# finger_jlink_r1_4.net
KiCad netlist of a schematic drawn in EAGLE
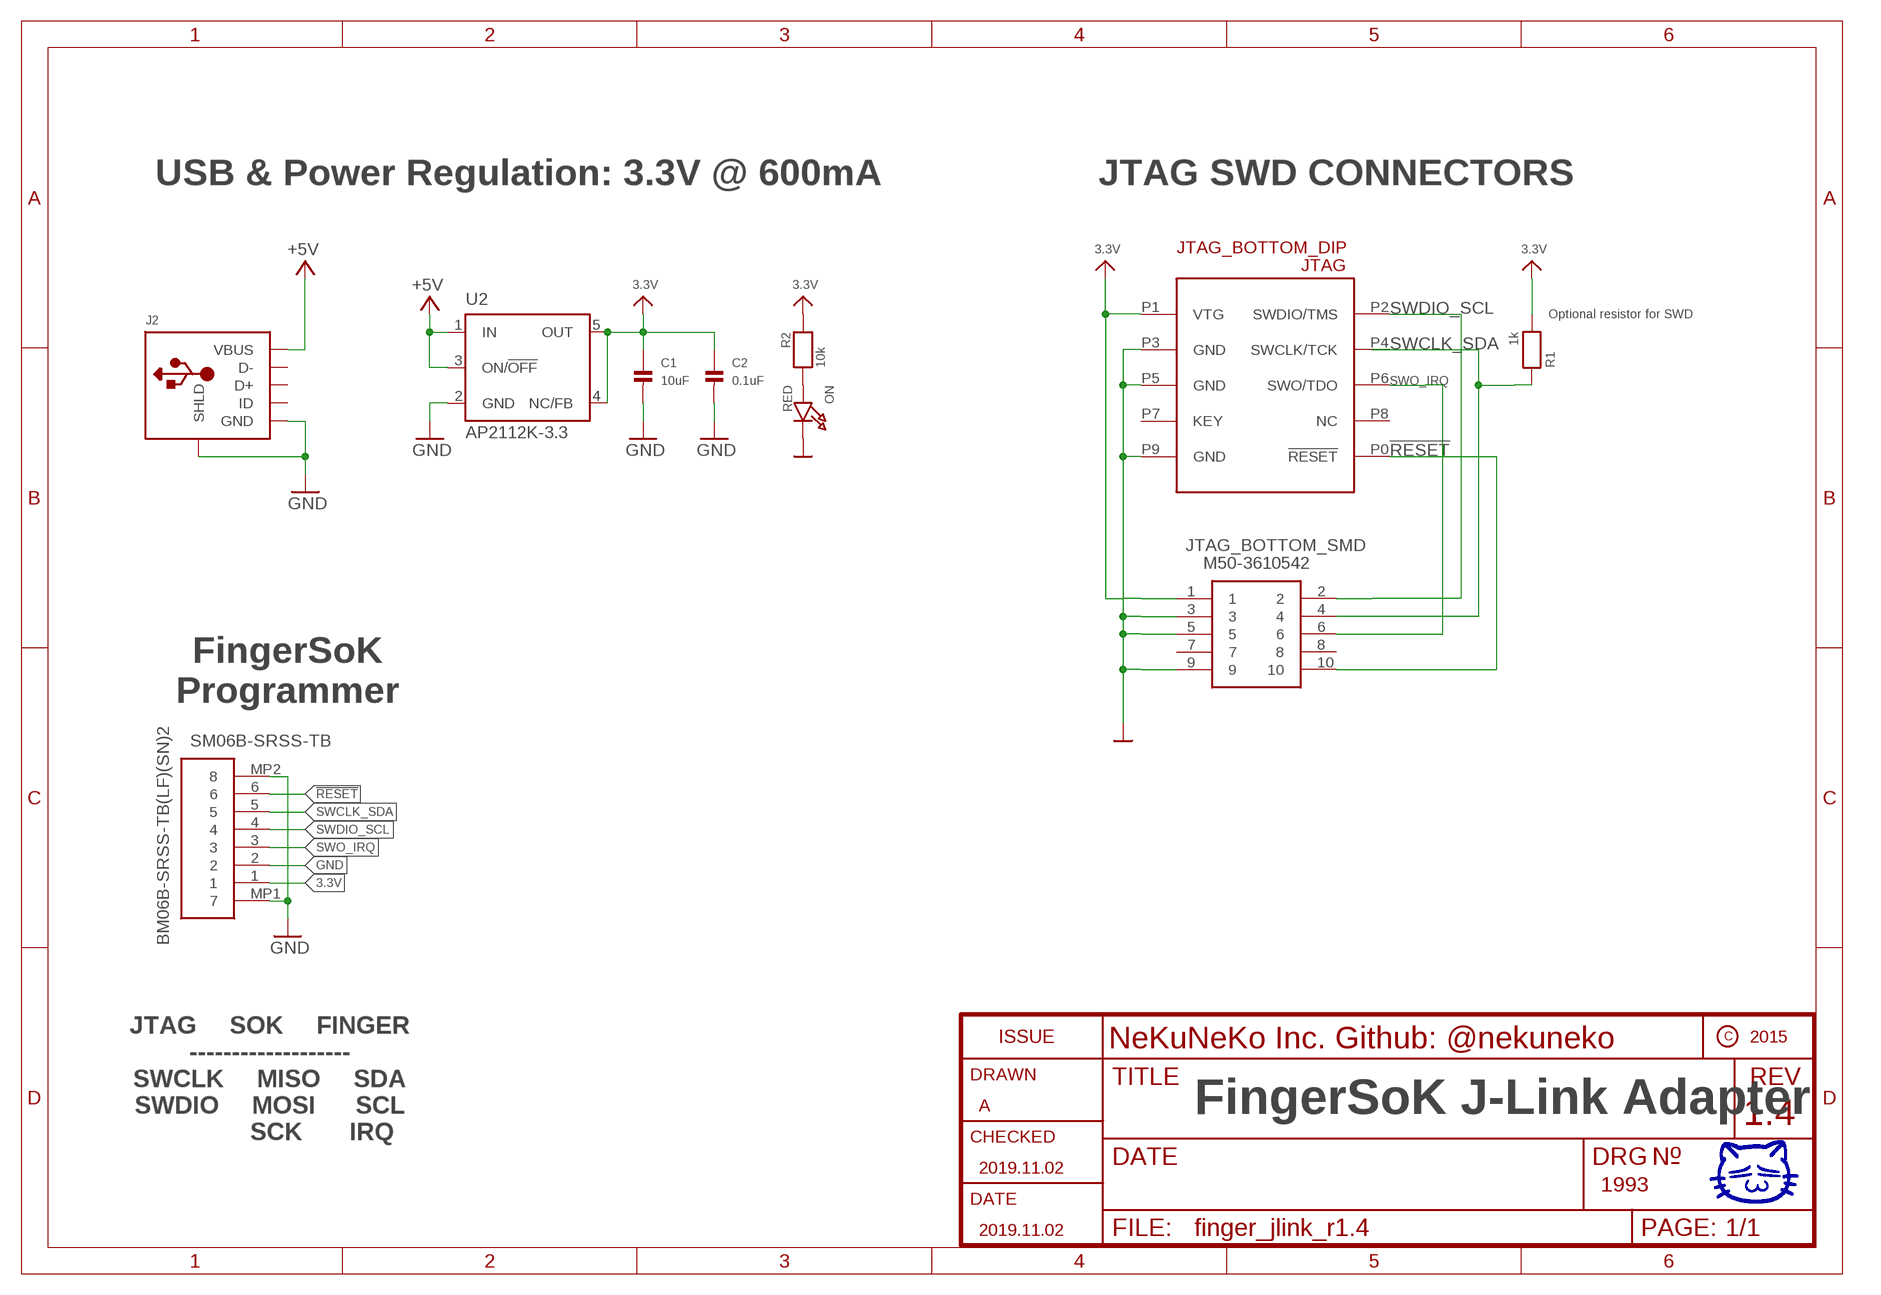
[diagram p0: schematic, sheet 1]

(export (version "E")
  (design (tool "Eeschema 10.0.6"))
  (components
    (comp (ref "C1")
      (value "10uF")
      (footprint "eagle-import:_0402")
      (libsource (lib "eagle-import") (part "CAP_CERAMIC_0402"))
    )
    (comp (ref "C2")
      (value "0.1uF")
      (footprint "eagle-import:_0402")
      (libsource (lib "eagle-import") (part "CAP_CERAMIC_0402"))
    )
    (comp (ref "J2")
      (value "FLAT_MICROUSB_ALIEXPRESS_TYPE_4")
      (footprint "eagle-import:USB_TYPE_4_105164-0001")
      (libsource (lib "eagle-import") (part "FLAT_MICROUSB_ALIEXPRESS_TYPE_4"))
    )
    (comp (ref "JTAG_BOTTOM_DIP")
      (value "JTAGICE3-CONNECTOR50MIL-THT")
      (footprint "eagle-import:JTAGICE3-50MIL")
      (libsource (lib "eagle-import") (part "JTAGICE3-CONNECTOR50MIL-THT"))
    )
    (comp (ref "JTAG_BOTTOM_SMD")
      (value "M50-3610542")
      (footprint "eagle-import:M503610542")
      (fields (field (name "MOUSER_PART_NUMBER") "855-M50-3610542"))
      (libsource (lib "eagle-import") (part "M50-3610542"))
    )
    (comp (ref "ON")
      (value "RED")
      (footprint "eagle-import:CHIPLED_0603")
      (libsource (lib "eagle-import") (part "LED0603"))
    )
    (comp (ref "R1")
      (value "1k")
      (footprint "eagle-import:_0402")
      (libsource (lib "eagle-import") (part "RESISTOR_0402"))
    )
    (comp (ref "R2")
      (value "10k")
      (footprint "eagle-import:_0402")
      (libsource (lib "eagle-import") (part "RESISTOR_0402"))
    )
    (comp (ref "SM06B-SRSS-TB")
      (value "BM06B-SRSS-TB(LF)(SN)2")
      (footprint "eagle-import:BM06B-SRSS-TB(LF)(SN)_2")
      (libsource (lib "eagle-import") (part "BM06B-SRSS-TB(LF)(SN)2"))
    )
    (comp (ref "U2")
      (value "AP2112K-3.3")
      (footprint "eagle-import:SOT23-DBV")
      (libsource (lib "eagle-import") (part "LP2985-XXDBVR33"))
    )
  )
  (nets
    (net (code "1") (name "+5V") (class "Default")
      (node (ref "J2") (pin "P$5") (pinfunction "VBUS_P$5") (pintype "power_in"))
      (node (ref "U2") (pin "1") (pinfunction "IN_1") (pintype "input"))
      (node (ref "U2") (pin "3") (pinfunction "ON/~{OFF}_3") (pintype "input"))
    )
    (net (code "2") (name "/~{RESET}") (class "Default")
      (node (ref "JTAG_BOTTOM_DIP") (pin "P0") (pinfunction "~{RESET}_P0") (pintype "bidirectional"))
      (node (ref "JTAG_BOTTOM_SMD") (pin "10") (pinfunction "10_10") (pintype "bidirectional"))
      (node (ref "SM06B-SRSS-TB") (pin "6") (pinfunction "6_6") (pintype "bidirectional"))
    )
    (net (code "3") (name "3.3V") (class "Default")
      (node (ref "C1") (pin "1") (pinfunction "P$1_1") (pintype "passive"))
      (node (ref "C2") (pin "1") (pinfunction "P$1_1") (pintype "passive"))
      (node (ref "JTAG_BOTTOM_DIP") (pin "P1") (pinfunction "VTG_P1") (pintype "bidirectional"))
      (node (ref "JTAG_BOTTOM_SMD") (pin "1") (pinfunction "1_1") (pintype "bidirectional"))
      (node (ref "R1") (pin "2") (pinfunction "2_2") (pintype "passive"))
      (node (ref "R2") (pin "2") (pinfunction "2_2") (pintype "passive"))
      (node (ref "SM06B-SRSS-TB") (pin "1") (pinfunction "1_1") (pintype "bidirectional"))
      (node (ref "U2") (pin "4") (pinfunction "NC/FB_4") (pintype "passive"))
      (node (ref "U2") (pin "5") (pinfunction "OUT_5") (pintype "passive"))
    )
    (net (code "4") (name "GND") (class "Default")
      (node (ref "C1") (pin "2") (pinfunction "P$2_2") (pintype "passive"))
      (node (ref "C2") (pin "2") (pinfunction "P$2_2") (pintype "passive"))
      (node (ref "J2") (pin "P$1") (pinfunction "GND_P$1") (pintype "power_in"))
      (node (ref "J2") (pin "P$8") (pinfunction "SHLD_P$8") (pintype "power_in"))
      (node (ref "J2") (pin "P$9") (pinfunction "SHLD_P$9") (pintype "power_in"))
      (node (ref "JTAG_BOTTOM_DIP") (pin "P3") (pinfunction "GND_P3") (pintype "bidirectional"))
      (node (ref "JTAG_BOTTOM_DIP") (pin "P5") (pinfunction "GND_P5") (pintype "bidirectional"))
      (node (ref "JTAG_BOTTOM_DIP") (pin "P9") (pinfunction "GND_P9") (pintype "bidirectional"))
      (node (ref "JTAG_BOTTOM_SMD") (pin "3") (pinfunction "3_3") (pintype "bidirectional"))
      (node (ref "JTAG_BOTTOM_SMD") (pin "5") (pinfunction "5_5") (pintype "bidirectional"))
      (node (ref "JTAG_BOTTOM_SMD") (pin "9") (pinfunction "9_9") (pintype "bidirectional"))
      (node (ref "ON") (pin "C") (pinfunction "C_C") (pintype "passive"))
      (node (ref "SM06B-SRSS-TB") (pin "2") (pinfunction "2_2") (pintype "bidirectional"))
      (node (ref "SM06B-SRSS-TB") (pin "MP1") (pinfunction "7_MP1") (pintype "bidirectional"))
      (node (ref "SM06B-SRSS-TB") (pin "MP2") (pinfunction "8_MP2") (pintype "bidirectional"))
      (node (ref "U2") (pin "2") (pinfunction "GND_2") (pintype "power_in"))
    )
    (net (code "5") (name "Net-(ON-PadA)") (class "Default")
      (node (ref "ON") (pin "A") (pinfunction "A_A") (pintype "passive"))
      (node (ref "R2") (pin "1") (pinfunction "1_1") (pintype "passive"))
    )
    (net (code "6") (name "SWCLK_SDA") (class "Default")
      (node (ref "JTAG_BOTTOM_DIP") (pin "P4") (pinfunction "SWCLK/TCK_P4") (pintype "bidirectional"))
      (node (ref "JTAG_BOTTOM_SMD") (pin "4") (pinfunction "4_4") (pintype "bidirectional"))
      (node (ref "R1") (pin "1") (pinfunction "1_1") (pintype "passive"))
      (node (ref "SM06B-SRSS-TB") (pin "5") (pinfunction "5_5") (pintype "bidirectional"))
    )
    (net (code "7") (name "SWDIO_SCL") (class "Default")
      (node (ref "JTAG_BOTTOM_DIP") (pin "P2") (pinfunction "SWDIO/TMS_P2") (pintype "bidirectional"))
      (node (ref "JTAG_BOTTOM_SMD") (pin "2") (pinfunction "2_2") (pintype "bidirectional"))
      (node (ref "SM06B-SRSS-TB") (pin "4") (pinfunction "4_4") (pintype "bidirectional"))
    )
    (net (code "8") (name "SWO_IRQ") (class "Default")
      (node (ref "JTAG_BOTTOM_DIP") (pin "P6") (pinfunction "SWO/TDO_P6") (pintype "bidirectional"))
      (node (ref "JTAG_BOTTOM_SMD") (pin "6") (pinfunction "6_6") (pintype "bidirectional"))
      (node (ref "SM06B-SRSS-TB") (pin "3") (pinfunction "3_3") (pintype "bidirectional"))
    )
    (net (code "9") (name "unconnected-(J2-D+-PadP$3)") (class "Default")
      (node (ref "J2") (pin "P$3") (pinfunction "D+_P$3") (pintype "bidirectional"))
    )
    (net (code "10") (name "unconnected-(J2-D--PadP$4)") (class "Default")
      (node (ref "J2") (pin "P$4") (pinfunction "D-_P$4") (pintype "bidirectional"))
    )
    (net (code "11") (name "unconnected-(J2-ID-PadP$2)") (class "Default")
      (node (ref "J2") (pin "P$2") (pinfunction "ID_P$2") (pintype "bidirectional"))
    )
    (net (code "12") (name "unconnected-(JTAG_BOTTOM_DIP-KEY-PadP7)") (class "Default")
      (node (ref "JTAG_BOTTOM_DIP") (pin "P7") (pinfunction "KEY_P7") (pintype "bidirectional"))
    )
    (net (code "13") (name "unconnected-(JTAG_BOTTOM_DIP-NC-PadP8)") (class "Default")
      (node (ref "JTAG_BOTTOM_DIP") (pin "P8") (pinfunction "NC_P8") (pintype "bidirectional"))
    )
    (net (code "14") (name "unconnected-(JTAG_BOTTOM_SMD-Pad7)") (class "Default")
      (node (ref "JTAG_BOTTOM_SMD") (pin "7") (pinfunction "7_7") (pintype "bidirectional"))
    )
    (net (code "15") (name "unconnected-(JTAG_BOTTOM_SMD-Pad8)") (class "Default")
      (node (ref "JTAG_BOTTOM_SMD") (pin "8") (pinfunction "8_8") (pintype "bidirectional"))
    )
  )
)
